# breakout_board.net
KiCad netlist of a schematic drawn in EAGLE
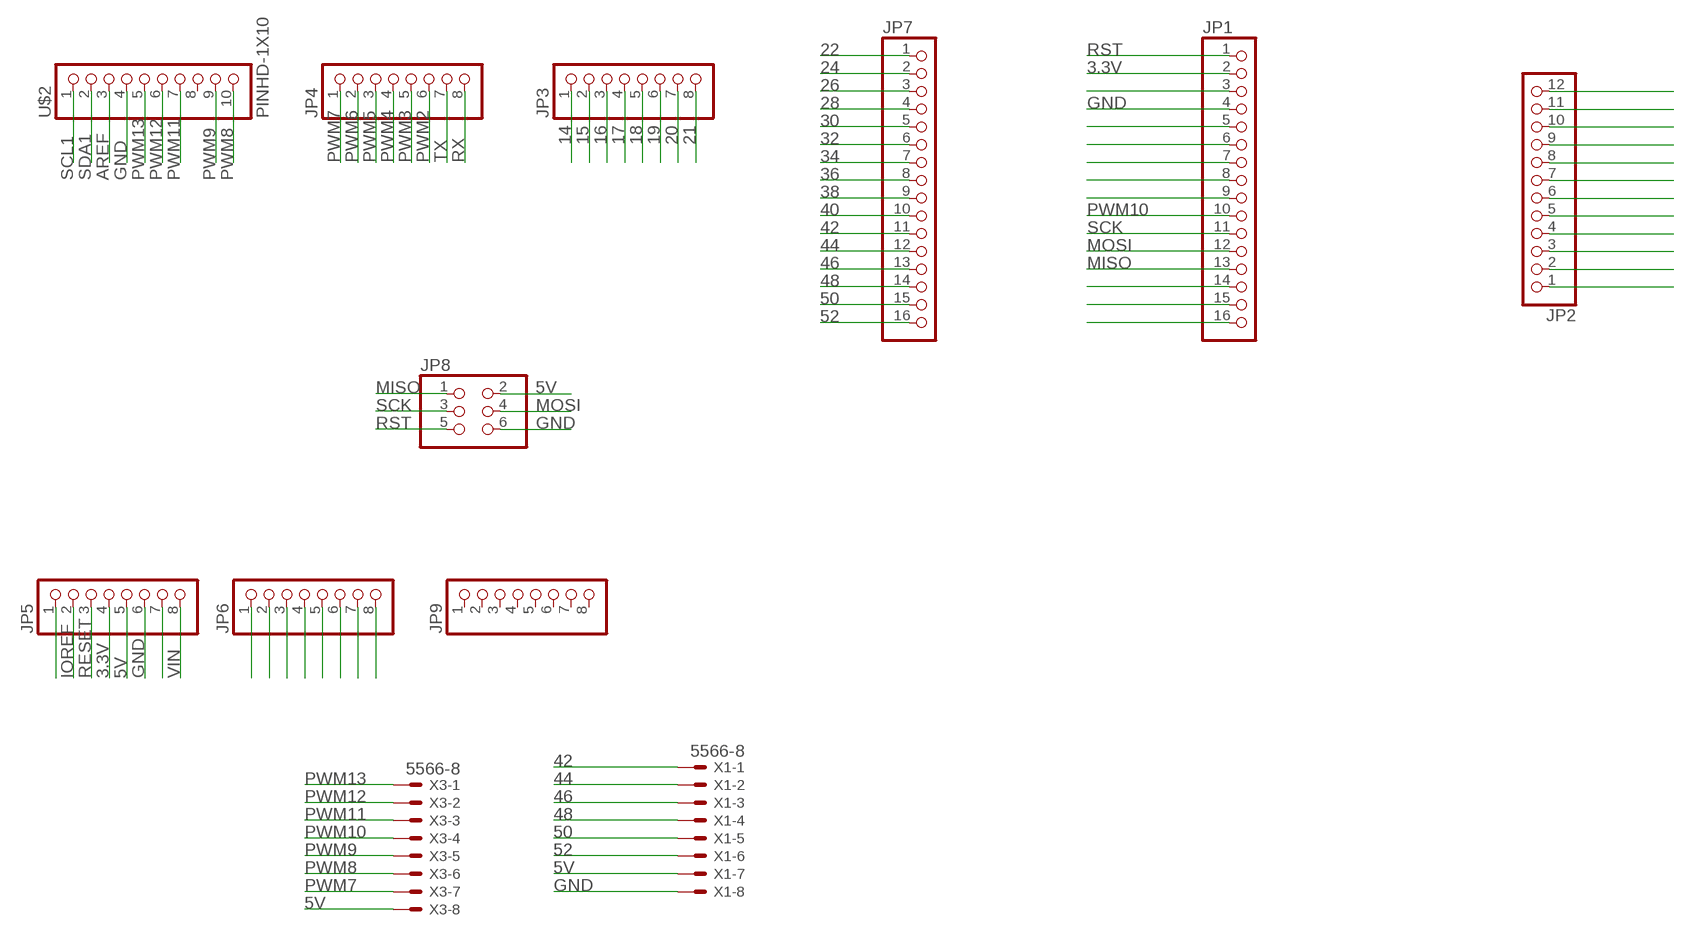
[diagram p0: schematic, sheet 1]

(export (version "E")
  (design (tool "Eeschema 10.0.6"))
  (components
    (comp (ref "JP1")
      (value "PINHD-1X16")
      (footprint "eagle-import:1X16")
      (libsource (lib "eagle-import") (part "PINHD-1X16"))
    )
    (comp (ref "JP2")
      (value "PINHD-1X12")
      (footprint "eagle-import:1X12")
      (libsource (lib "eagle-import") (part "PINHD-1X12"))
    )
    (comp (ref "JP3")
      (value "PINHD-1X8BIG")
      (footprint "eagle-import:1X08-BIG")
      (libsource (lib "eagle-import") (part "PINHD-1X8BIG"))
    )
    (comp (ref "JP4")
      (value "PINHD-1X8BIG")
      (footprint "eagle-import:1X08-BIG")
      (libsource (lib "eagle-import") (part "PINHD-1X8BIG"))
    )
    (comp (ref "JP5")
      (value "PINHD-1X8BIG")
      (footprint "eagle-import:1X08-BIG")
      (libsource (lib "eagle-import") (part "PINHD-1X8BIG"))
    )
    (comp (ref "JP6")
      (value "PINHD-1X8BIG")
      (footprint "eagle-import:1X08-BIG")
      (libsource (lib "eagle-import") (part "PINHD-1X8BIG"))
    )
    (comp (ref "JP7")
      (value "PINHD-1X16")
      (footprint "eagle-import:1X16")
      (libsource (lib "eagle-import") (part "PINHD-1X16"))
    )
    (comp (ref "JP8")
      (value "PINHD-2X3")
      (footprint "eagle-import:2X03")
      (libsource (lib "eagle-import") (part "PINHD-2X3"))
    )
    (comp (ref "JP9")
      (value "PINHD-1X8BIG")
      (footprint "eagle-import:1X08-BIG")
      (libsource (lib "eagle-import") (part "PINHD-1X8BIG"))
    )
    (comp (ref "U$2")
      (value "PINHD-1X10")
      (footprint "eagle-import:1X10-BIG")
      (libsource (lib "eagle-import") (part "PINHD-1X10"))
    )
    (comp (ref "X1")
      (value "5566-8")
      (footprint "eagle-import:5566-8")
      (fields (field (name "MF") "MOLEX"))
      (libsource (lib "eagle-import") (part "5566-8"))
    )
    (comp (ref "X3")
      (value "5566-8")
      (footprint "eagle-import:5566-8")
      (fields (field (name "MF") "MOLEX"))
      (libsource (lib "eagle-import") (part "5566-8"))
    )
  )
  (nets
    (net (code "1") (name "/3.3V") (class "Default")
      (node (ref "JP1") (pin "2") (pinfunction "2_2") (pintype "passive"))
      (node (ref "JP5") (pin "4") (pinfunction "4_4") (pintype "passive"))
    )
    (net (code "2") (name "/5V") (class "Default")
      (node (ref "JP5") (pin "5") (pinfunction "5_5") (pintype "passive"))
      (node (ref "JP8") (pin "2") (pinfunction "2_2") (pintype "passive"))
      (node (ref "X1") (pin "7") (pinfunction "S_7") (pintype "passive"))
      (node (ref "X3") (pin "8") (pinfunction "S_8") (pintype "passive"))
    )
    (net (code "3") (name "/14") (class "Default")
      (node (ref "JP3") (pin "1") (pinfunction "1_1") (pintype "passive"))
    )
    (net (code "4") (name "/15") (class "Default")
      (node (ref "JP3") (pin "2") (pinfunction "2_2") (pintype "passive"))
    )
    (net (code "5") (name "/16") (class "Default")
      (node (ref "JP3") (pin "3") (pinfunction "3_3") (pintype "passive"))
    )
    (net (code "6") (name "/17") (class "Default")
      (node (ref "JP3") (pin "4") (pinfunction "4_4") (pintype "passive"))
    )
    (net (code "7") (name "/18") (class "Default")
      (node (ref "JP3") (pin "5") (pinfunction "5_5") (pintype "passive"))
    )
    (net (code "8") (name "/19") (class "Default")
      (node (ref "JP3") (pin "6") (pinfunction "6_6") (pintype "passive"))
    )
    (net (code "9") (name "/20") (class "Default")
      (node (ref "JP3") (pin "7") (pinfunction "7_7") (pintype "passive"))
    )
    (net (code "10") (name "/21") (class "Default")
      (node (ref "JP3") (pin "8") (pinfunction "8_8") (pintype "passive"))
    )
    (net (code "11") (name "/22") (class "Default")
      (node (ref "JP7") (pin "1") (pinfunction "1_1") (pintype "passive"))
    )
    (net (code "12") (name "/24") (class "Default")
      (node (ref "JP7") (pin "2") (pinfunction "2_2") (pintype "passive"))
    )
    (net (code "13") (name "/26") (class "Default")
      (node (ref "JP7") (pin "3") (pinfunction "3_3") (pintype "passive"))
    )
    (net (code "14") (name "/28") (class "Default")
      (node (ref "JP7") (pin "4") (pinfunction "4_4") (pintype "passive"))
    )
    (net (code "15") (name "/30") (class "Default")
      (node (ref "JP7") (pin "5") (pinfunction "5_5") (pintype "passive"))
    )
    (net (code "16") (name "/32") (class "Default")
      (node (ref "JP7") (pin "6") (pinfunction "6_6") (pintype "passive"))
    )
    (net (code "17") (name "/34") (class "Default")
      (node (ref "JP7") (pin "7") (pinfunction "7_7") (pintype "passive"))
    )
    (net (code "18") (name "/36") (class "Default")
      (node (ref "JP7") (pin "8") (pinfunction "8_8") (pintype "passive"))
    )
    (net (code "19") (name "/38") (class "Default")
      (node (ref "JP7") (pin "9") (pinfunction "9_9") (pintype "passive"))
    )
    (net (code "20") (name "/40") (class "Default")
      (node (ref "JP7") (pin "10") (pinfunction "10_10") (pintype "passive"))
    )
    (net (code "21") (name "/42") (class "Default")
      (node (ref "JP7") (pin "11") (pinfunction "11_11") (pintype "passive"))
      (node (ref "X1") (pin "1") (pinfunction "S_1") (pintype "passive"))
    )
    (net (code "22") (name "/44") (class "Default")
      (node (ref "JP7") (pin "12") (pinfunction "12_12") (pintype "passive"))
      (node (ref "X1") (pin "2") (pinfunction "S_2") (pintype "passive"))
    )
    (net (code "23") (name "/46") (class "Default")
      (node (ref "JP7") (pin "13") (pinfunction "13_13") (pintype "passive"))
      (node (ref "X1") (pin "3") (pinfunction "S_3") (pintype "passive"))
    )
    (net (code "24") (name "/48") (class "Default")
      (node (ref "JP7") (pin "14") (pinfunction "14_14") (pintype "passive"))
      (node (ref "X1") (pin "4") (pinfunction "S_4") (pintype "passive"))
    )
    (net (code "25") (name "/50") (class "Default")
      (node (ref "JP7") (pin "15") (pinfunction "15_15") (pintype "passive"))
      (node (ref "X1") (pin "5") (pinfunction "S_5") (pintype "passive"))
    )
    (net (code "26") (name "/52") (class "Default")
      (node (ref "JP7") (pin "16") (pinfunction "16_16") (pintype "passive"))
      (node (ref "X1") (pin "6") (pinfunction "S_6") (pintype "passive"))
    )
    (net (code "27") (name "/AREF") (class "Default")
      (node (ref "U$2") (pin "3") (pinfunction "3_3") (pintype "passive"))
    )
    (net (code "28") (name "/GND") (class "Default")
      (node (ref "JP1") (pin "4") (pinfunction "4_4") (pintype "passive"))
      (node (ref "JP5") (pin "6") (pinfunction "6_6") (pintype "passive"))
      (node (ref "JP8") (pin "6") (pinfunction "6_6") (pintype "passive"))
      (node (ref "U$2") (pin "4") (pinfunction "4_4") (pintype "passive"))
      (node (ref "X1") (pin "8") (pinfunction "S_8") (pintype "passive"))
    )
    (net (code "29") (name "/IOREF") (class "Default")
      (node (ref "JP5") (pin "2") (pinfunction "2_2") (pintype "passive"))
    )
    (net (code "30") (name "/MISO") (class "Default")
      (node (ref "JP1") (pin "13") (pinfunction "13_13") (pintype "passive"))
      (node (ref "JP8") (pin "1") (pinfunction "1_1") (pintype "passive"))
    )
    (net (code "31") (name "/MOSI") (class "Default")
      (node (ref "JP1") (pin "12") (pinfunction "12_12") (pintype "passive"))
      (node (ref "JP8") (pin "4") (pinfunction "4_4") (pintype "passive"))
    )
    (net (code "32") (name "/PWM2") (class "Default")
      (node (ref "JP4") (pin "6") (pinfunction "6_6") (pintype "passive"))
    )
    (net (code "33") (name "/PWM3") (class "Default")
      (node (ref "JP4") (pin "5") (pinfunction "5_5") (pintype "passive"))
    )
    (net (code "34") (name "/PWM4") (class "Default")
      (node (ref "JP4") (pin "4") (pinfunction "4_4") (pintype "passive"))
    )
    (net (code "35") (name "/PWM5") (class "Default")
      (node (ref "JP4") (pin "3") (pinfunction "3_3") (pintype "passive"))
    )
    (net (code "36") (name "/PWM6") (class "Default")
      (node (ref "JP4") (pin "2") (pinfunction "2_2") (pintype "passive"))
    )
    (net (code "37") (name "/PWM7") (class "Default")
      (node (ref "JP4") (pin "1") (pinfunction "1_1") (pintype "passive"))
      (node (ref "X3") (pin "7") (pinfunction "S_7") (pintype "passive"))
    )
    (net (code "38") (name "/PWM8") (class "Default")
      (node (ref "U$2") (pin "10") (pinfunction "10_10") (pintype "passive"))
      (node (ref "X3") (pin "6") (pinfunction "S_6") (pintype "passive"))
    )
    (net (code "39") (name "/PWM9") (class "Default")
      (node (ref "U$2") (pin "9") (pinfunction "9_9") (pintype "passive"))
      (node (ref "X3") (pin "5") (pinfunction "S_5") (pintype "passive"))
    )
    (net (code "40") (name "/PWM10") (class "Default")
      (node (ref "JP1") (pin "10") (pinfunction "10_10") (pintype "passive"))
      (node (ref "X3") (pin "4") (pinfunction "S_4") (pintype "passive"))
    )
    (net (code "41") (name "/PWM11") (class "Default")
      (node (ref "U$2") (pin "7") (pinfunction "7_7") (pintype "passive"))
      (node (ref "X3") (pin "3") (pinfunction "S_3") (pintype "passive"))
    )
    (net (code "42") (name "/PWM12") (class "Default")
      (node (ref "U$2") (pin "6") (pinfunction "6_6") (pintype "passive"))
      (node (ref "X3") (pin "2") (pinfunction "S_2") (pintype "passive"))
    )
    (net (code "43") (name "/PWM13") (class "Default")
      (node (ref "U$2") (pin "5") (pinfunction "5_5") (pintype "passive"))
      (node (ref "X3") (pin "1") (pinfunction "S_1") (pintype "passive"))
    )
    (net (code "44") (name "/RESET") (class "Default")
      (node (ref "JP5") (pin "3") (pinfunction "3_3") (pintype "passive"))
    )
    (net (code "45") (name "/RST") (class "Default")
      (node (ref "JP1") (pin "1") (pinfunction "1_1") (pintype "passive"))
      (node (ref "JP8") (pin "5") (pinfunction "5_5") (pintype "passive"))
    )
    (net (code "46") (name "/RX") (class "Default")
      (node (ref "JP4") (pin "8") (pinfunction "8_8") (pintype "passive"))
    )
    (net (code "47") (name "/SCK") (class "Default")
      (node (ref "JP1") (pin "11") (pinfunction "11_11") (pintype "passive"))
      (node (ref "JP8") (pin "3") (pinfunction "3_3") (pintype "passive"))
    )
    (net (code "48") (name "/SCL1") (class "Default")
      (node (ref "U$2") (pin "1") (pinfunction "1_1") (pintype "passive"))
    )
    (net (code "49") (name "/SDA1") (class "Default")
      (node (ref "U$2") (pin "2") (pinfunction "2_2") (pintype "passive"))
    )
    (net (code "50") (name "/TX") (class "Default")
      (node (ref "JP4") (pin "7") (pinfunction "7_7") (pintype "passive"))
    )
    (net (code "51") (name "/VIN") (class "Default")
      (node (ref "JP5") (pin "8") (pinfunction "8_8") (pintype "passive"))
    )
    (net (code "52") (name "unconnected-(JP1-Pad3)") (class "Default")
      (node (ref "JP1") (pin "3") (pinfunction "3_3") (pintype "passive"))
    )
    (net (code "53") (name "unconnected-(JP1-Pad5)") (class "Default")
      (node (ref "JP1") (pin "5") (pinfunction "5_5") (pintype "passive"))
    )
    (net (code "54") (name "unconnected-(JP1-Pad6)") (class "Default")
      (node (ref "JP1") (pin "6") (pinfunction "6_6") (pintype "passive"))
    )
    (net (code "55") (name "unconnected-(JP1-Pad7)") (class "Default")
      (node (ref "JP1") (pin "7") (pinfunction "7_7") (pintype "passive"))
    )
    (net (code "56") (name "unconnected-(JP1-Pad8)") (class "Default")
      (node (ref "JP1") (pin "8") (pinfunction "8_8") (pintype "passive"))
    )
    (net (code "57") (name "unconnected-(JP1-Pad9)") (class "Default")
      (node (ref "JP1") (pin "9") (pinfunction "9_9") (pintype "passive"))
    )
    (net (code "58") (name "unconnected-(JP1-Pad14)") (class "Default")
      (node (ref "JP1") (pin "14") (pinfunction "14_14") (pintype "passive"))
    )
    (net (code "59") (name "unconnected-(JP1-Pad15)") (class "Default")
      (node (ref "JP1") (pin "15") (pinfunction "15_15") (pintype "passive"))
    )
    (net (code "60") (name "unconnected-(JP1-Pad16)") (class "Default")
      (node (ref "JP1") (pin "16") (pinfunction "16_16") (pintype "passive"))
    )
    (net (code "61") (name "unconnected-(JP2-Pad1)") (class "Default")
      (node (ref "JP2") (pin "1") (pinfunction "1_1") (pintype "passive"))
    )
    (net (code "62") (name "unconnected-(JP2-Pad2)") (class "Default")
      (node (ref "JP2") (pin "2") (pinfunction "2_2") (pintype "passive"))
    )
    (net (code "63") (name "unconnected-(JP2-Pad3)") (class "Default")
      (node (ref "JP2") (pin "3") (pinfunction "3_3") (pintype "passive"))
    )
    (net (code "64") (name "unconnected-(JP2-Pad4)") (class "Default")
      (node (ref "JP2") (pin "4") (pinfunction "4_4") (pintype "passive"))
    )
    (net (code "65") (name "unconnected-(JP2-Pad5)") (class "Default")
      (node (ref "JP2") (pin "5") (pinfunction "5_5") (pintype "passive"))
    )
    (net (code "66") (name "unconnected-(JP2-Pad6)") (class "Default")
      (node (ref "JP2") (pin "6") (pinfunction "6_6") (pintype "passive"))
    )
    (net (code "67") (name "unconnected-(JP2-Pad7)") (class "Default")
      (node (ref "JP2") (pin "7") (pinfunction "7_7") (pintype "passive"))
    )
    (net (code "68") (name "unconnected-(JP2-Pad8)") (class "Default")
      (node (ref "JP2") (pin "8") (pinfunction "8_8") (pintype "passive"))
    )
    (net (code "69") (name "unconnected-(JP2-Pad9)") (class "Default")
      (node (ref "JP2") (pin "9") (pinfunction "9_9") (pintype "passive"))
    )
    (net (code "70") (name "unconnected-(JP2-Pad10)") (class "Default")
      (node (ref "JP2") (pin "10") (pinfunction "10_10") (pintype "passive"))
    )
    (net (code "71") (name "unconnected-(JP2-Pad11)") (class "Default")
      (node (ref "JP2") (pin "11") (pinfunction "11_11") (pintype "passive"))
    )
    (net (code "72") (name "unconnected-(JP2-Pad12)") (class "Default")
      (node (ref "JP2") (pin "12") (pinfunction "12_12") (pintype "passive"))
    )
    (net (code "73") (name "unconnected-(JP5-Pad1)") (class "Default")
      (node (ref "JP5") (pin "1") (pinfunction "1_1") (pintype "passive"))
    )
    (net (code "74") (name "unconnected-(JP5-Pad7)") (class "Default")
      (node (ref "JP5") (pin "7") (pinfunction "7_7") (pintype "passive"))
    )
    (net (code "75") (name "unconnected-(JP6-Pad1)") (class "Default")
      (node (ref "JP6") (pin "1") (pinfunction "1_1") (pintype "passive"))
    )
    (net (code "76") (name "unconnected-(JP6-Pad2)") (class "Default")
      (node (ref "JP6") (pin "2") (pinfunction "2_2") (pintype "passive"))
    )
    (net (code "77") (name "unconnected-(JP6-Pad3)") (class "Default")
      (node (ref "JP6") (pin "3") (pinfunction "3_3") (pintype "passive"))
    )
    (net (code "78") (name "unconnected-(JP6-Pad4)") (class "Default")
      (node (ref "JP6") (pin "4") (pinfunction "4_4") (pintype "passive"))
    )
    (net (code "79") (name "unconnected-(JP6-Pad5)") (class "Default")
      (node (ref "JP6") (pin "5") (pinfunction "5_5") (pintype "passive"))
    )
    (net (code "80") (name "unconnected-(JP6-Pad6)") (class "Default")
      (node (ref "JP6") (pin "6") (pinfunction "6_6") (pintype "passive"))
    )
    (net (code "81") (name "unconnected-(JP6-Pad7)") (class "Default")
      (node (ref "JP6") (pin "7") (pinfunction "7_7") (pintype "passive"))
    )
    (net (code "82") (name "unconnected-(JP6-Pad8)") (class "Default")
      (node (ref "JP6") (pin "8") (pinfunction "8_8") (pintype "passive"))
    )
    (net (code "83") (name "unconnected-(JP9-Pad1)") (class "Default")
      (node (ref "JP9") (pin "1") (pinfunction "1_1") (pintype "passive"))
    )
    (net (code "84") (name "unconnected-(JP9-Pad2)") (class "Default")
      (node (ref "JP9") (pin "2") (pinfunction "2_2") (pintype "passive"))
    )
    (net (code "85") (name "unconnected-(JP9-Pad3)") (class "Default")
      (node (ref "JP9") (pin "3") (pinfunction "3_3") (pintype "passive"))
    )
    (net (code "86") (name "unconnected-(JP9-Pad4)") (class "Default")
      (node (ref "JP9") (pin "4") (pinfunction "4_4") (pintype "passive"))
    )
    (net (code "87") (name "unconnected-(JP9-Pad5)") (class "Default")
      (node (ref "JP9") (pin "5") (pinfunction "5_5") (pintype "passive"))
    )
    (net (code "88") (name "unconnected-(JP9-Pad6)") (class "Default")
      (node (ref "JP9") (pin "6") (pinfunction "6_6") (pintype "passive"))
    )
    (net (code "89") (name "unconnected-(JP9-Pad7)") (class "Default")
      (node (ref "JP9") (pin "7") (pinfunction "7_7") (pintype "passive"))
    )
    (net (code "90") (name "unconnected-(JP9-Pad8)") (class "Default")
      (node (ref "JP9") (pin "8") (pinfunction "8_8") (pintype "passive"))
    )
    (net (code "91") (name "unconnected-(U$2-Pad8)") (class "Default")
      (node (ref "U$2") (pin "8") (pinfunction "8_8") (pintype "passive"))
    )
  )
)
